# S181C.net
KiCad netlist of a schematic drawn in EAGLE
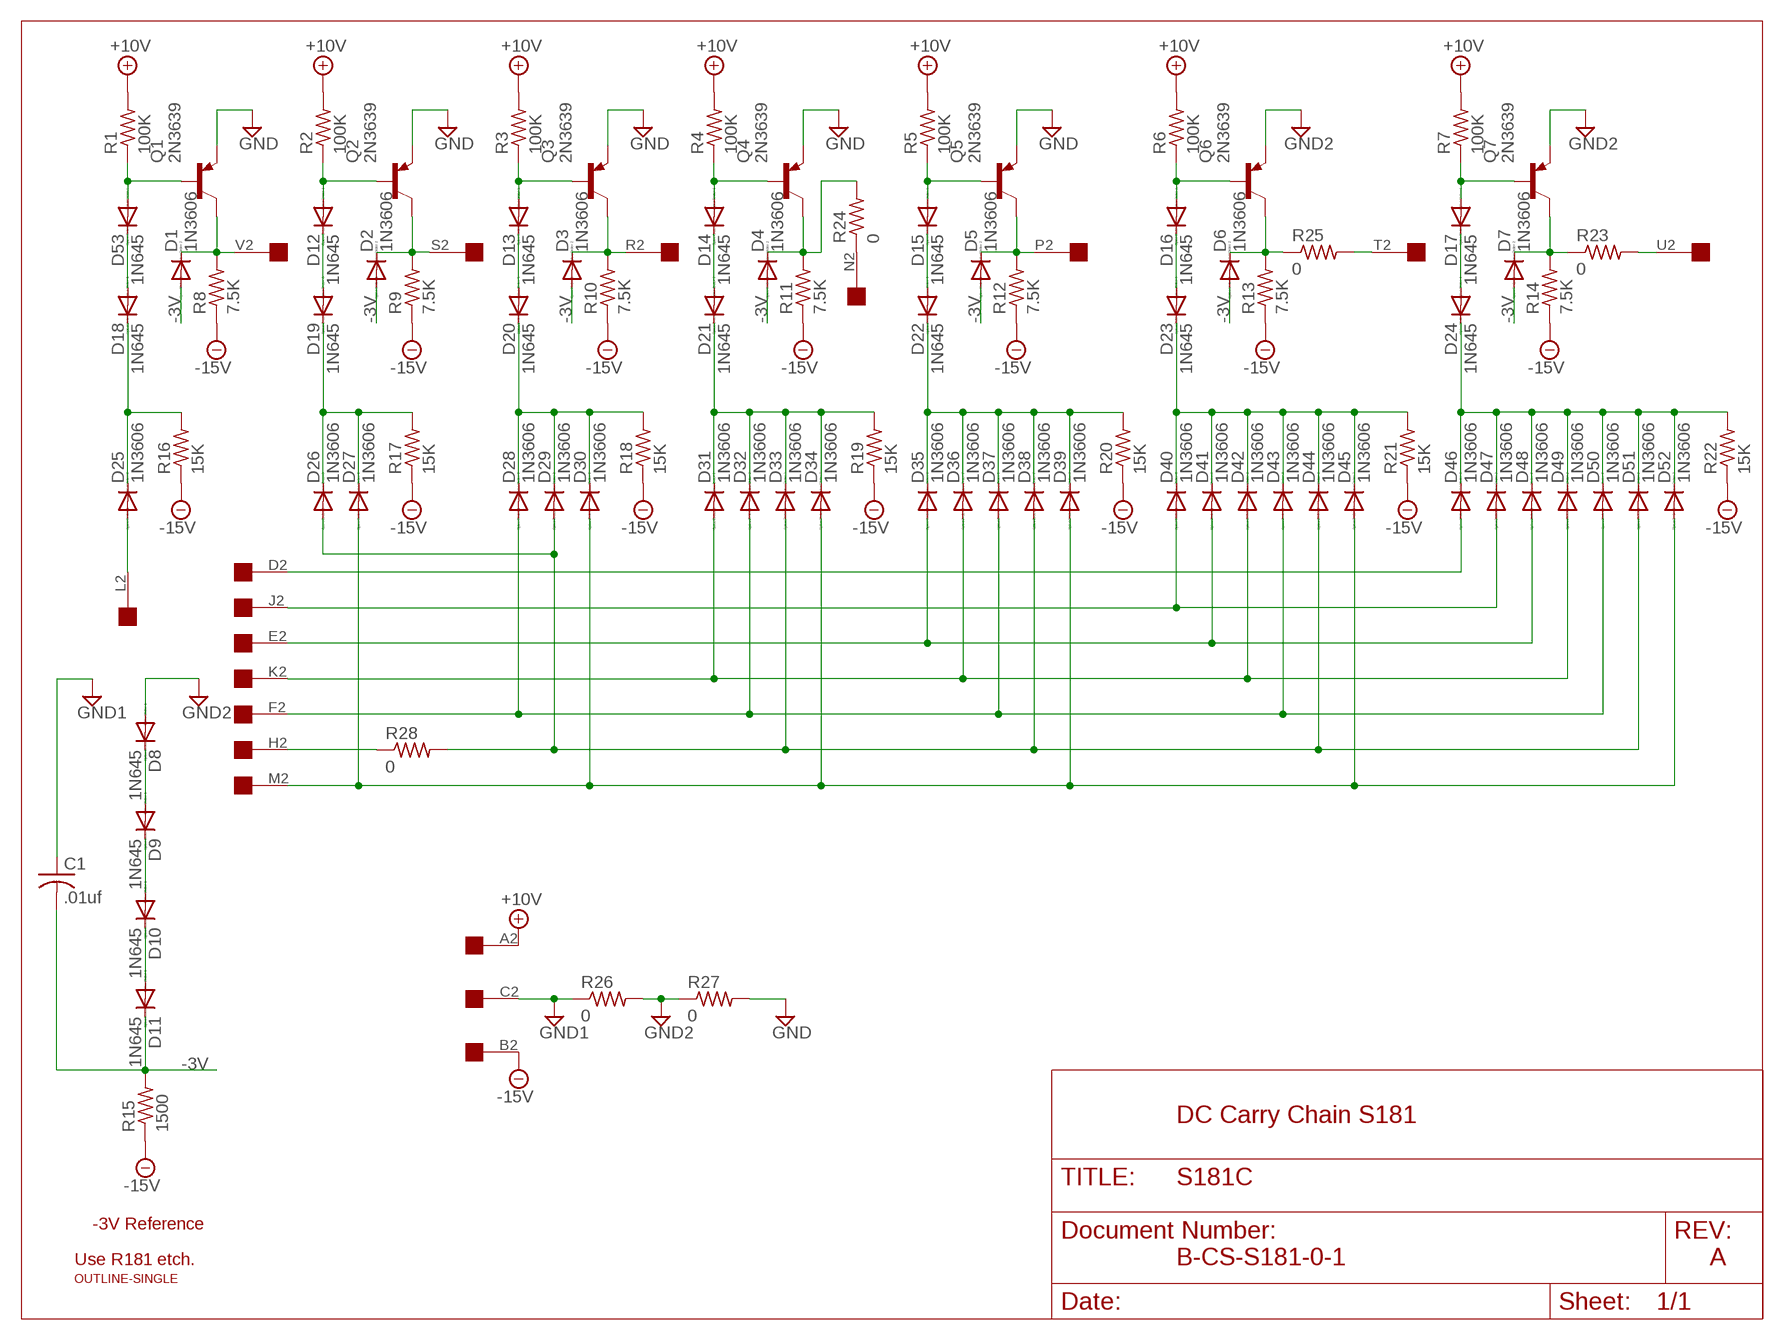
[diagram p0: schematic, sheet 1]

(export (version "E")
  (design (tool "Eeschema 10.0.6"))
  (components
    (comp (ref "C1")
      (value ".01uf")
      (footprint "eagle-import:C050-025X075")
      (libsource (lib "eagle-import") (part "C-US050-025X075"))
    )
    (comp (ref "D1")
      (value "1N3606")
      (footprint "eagle-import:DO35-10")
      (libsource (lib "eagle-import") (part "1N4148DO35-10"))
    )
    (comp (ref "D2")
      (value "1N3606")
      (footprint "eagle-import:DO35-10")
      (libsource (lib "eagle-import") (part "1N4148DO35-10"))
    )
    (comp (ref "D3")
      (value "1N3606")
      (footprint "eagle-import:DO35-10")
      (libsource (lib "eagle-import") (part "1N4148DO35-10"))
    )
    (comp (ref "D4")
      (value "1N3606")
      (footprint "eagle-import:DO35-10")
      (libsource (lib "eagle-import") (part "1N4148DO35-10"))
    )
    (comp (ref "D5")
      (value "1N3606")
      (footprint "eagle-import:DO35-10")
      (libsource (lib "eagle-import") (part "1N4148DO35-10"))
    )
    (comp (ref "D6")
      (value "1N3606")
      (footprint "eagle-import:DO35-10")
      (libsource (lib "eagle-import") (part "1N4148DO35-10"))
    )
    (comp (ref "D7")
      (value "1N3606")
      (footprint "eagle-import:DO35-10")
      (libsource (lib "eagle-import") (part "1N4148DO35-10"))
    )
    (comp (ref "D8")
      (value "1N645")
      (footprint "eagle-import:DO35-10")
      (libsource (lib "eagle-import") (part "1N4148DO35-10"))
    )
    (comp (ref "D9")
      (value "1N645")
      (footprint "eagle-import:DO35-10")
      (libsource (lib "eagle-import") (part "1N4148DO35-10"))
    )
    (comp (ref "D10")
      (value "1N645")
      (footprint "eagle-import:DO35-10")
      (libsource (lib "eagle-import") (part "1N4148DO35-10"))
    )
    (comp (ref "D11")
      (value "1N645")
      (footprint "eagle-import:DO35-10")
      (libsource (lib "eagle-import") (part "1N4148DO35-10"))
    )
    (comp (ref "D12")
      (value "1N645")
      (footprint "eagle-import:DO35-10")
      (libsource (lib "eagle-import") (part "1N4148DO35-10"))
    )
    (comp (ref "D13")
      (value "1N645")
      (footprint "eagle-import:DO35-10")
      (libsource (lib "eagle-import") (part "1N4148DO35-10"))
    )
    (comp (ref "D14")
      (value "1N645")
      (footprint "eagle-import:DO35-10")
      (libsource (lib "eagle-import") (part "1N4148DO35-10"))
    )
    (comp (ref "D15")
      (value "1N645")
      (footprint "eagle-import:DO35-10")
      (libsource (lib "eagle-import") (part "1N4148DO35-10"))
    )
    (comp (ref "D16")
      (value "1N645")
      (footprint "eagle-import:DO35-10")
      (libsource (lib "eagle-import") (part "1N4148DO35-10"))
    )
    (comp (ref "D17")
      (value "1N645")
      (footprint "eagle-import:DO35-10")
      (libsource (lib "eagle-import") (part "1N4148DO35-10"))
    )
    (comp (ref "D18")
      (value "1N645")
      (footprint "eagle-import:DO35-10")
      (libsource (lib "eagle-import") (part "1N4148DO35-10"))
    )
    (comp (ref "D19")
      (value "1N645")
      (footprint "eagle-import:DO35-10")
      (libsource (lib "eagle-import") (part "1N4148DO35-10"))
    )
    (comp (ref "D20")
      (value "1N645")
      (footprint "eagle-import:DO35-10")
      (libsource (lib "eagle-import") (part "1N4148DO35-10"))
    )
    (comp (ref "D21")
      (value "1N645")
      (footprint "eagle-import:DO35-10")
      (libsource (lib "eagle-import") (part "1N4148DO35-10"))
    )
    (comp (ref "D22")
      (value "1N645")
      (footprint "eagle-import:DO35-10")
      (libsource (lib "eagle-import") (part "1N4148DO35-10"))
    )
    (comp (ref "D23")
      (value "1N645")
      (footprint "eagle-import:DO35-10")
      (libsource (lib "eagle-import") (part "1N4148DO35-10"))
    )
    (comp (ref "D24")
      (value "1N645")
      (footprint "eagle-import:DO35-10")
      (libsource (lib "eagle-import") (part "1N4148DO35-10"))
    )
    (comp (ref "D25")
      (value "1N3606")
      (footprint "eagle-import:DO35-10")
      (libsource (lib "eagle-import") (part "1N4148DO35-10"))
    )
    (comp (ref "D26")
      (value "1N3606")
      (footprint "eagle-import:DO35-10")
      (libsource (lib "eagle-import") (part "1N4148DO35-10"))
    )
    (comp (ref "D27")
      (value "1N3606")
      (footprint "eagle-import:DO35-10")
      (libsource (lib "eagle-import") (part "1N4148DO35-10"))
    )
    (comp (ref "D28")
      (value "1N3606")
      (footprint "eagle-import:DO35-10")
      (libsource (lib "eagle-import") (part "1N4148DO35-10"))
    )
    (comp (ref "D29")
      (value "1N3606")
      (footprint "eagle-import:DO35-10")
      (libsource (lib "eagle-import") (part "1N4148DO35-10"))
    )
    (comp (ref "D30")
      (value "1N3606")
      (footprint "eagle-import:DO35-10")
      (libsource (lib "eagle-import") (part "1N4148DO35-10"))
    )
    (comp (ref "D31")
      (value "1N3606")
      (footprint "eagle-import:DO35-10")
      (libsource (lib "eagle-import") (part "1N4148DO35-10"))
    )
    (comp (ref "D32")
      (value "1N3606")
      (footprint "eagle-import:DO35-10")
      (libsource (lib "eagle-import") (part "1N4148DO35-10"))
    )
    (comp (ref "D33")
      (value "1N3606")
      (footprint "eagle-import:DO35-10")
      (libsource (lib "eagle-import") (part "1N4148DO35-10"))
    )
    (comp (ref "D34")
      (value "1N3606")
      (footprint "eagle-import:DO35-10")
      (libsource (lib "eagle-import") (part "1N4148DO35-10"))
    )
    (comp (ref "D35")
      (value "1N3606")
      (footprint "eagle-import:DO35-10")
      (libsource (lib "eagle-import") (part "1N4148DO35-10"))
    )
    (comp (ref "D36")
      (value "1N3606")
      (footprint "eagle-import:DO35-10")
      (libsource (lib "eagle-import") (part "1N4148DO35-10"))
    )
    (comp (ref "D37")
      (value "1N3606")
      (footprint "eagle-import:DO35-10")
      (libsource (lib "eagle-import") (part "1N4148DO35-10"))
    )
    (comp (ref "D38")
      (value "1N3606")
      (footprint "eagle-import:DO35-10")
      (libsource (lib "eagle-import") (part "1N4148DO35-10"))
    )
    (comp (ref "D39")
      (value "1N3606")
      (footprint "eagle-import:DO35-10")
      (libsource (lib "eagle-import") (part "1N4148DO35-10"))
    )
    (comp (ref "D40")
      (value "1N3606")
      (footprint "eagle-import:DO35-10")
      (libsource (lib "eagle-import") (part "1N4148DO35-10"))
    )
    (comp (ref "D41")
      (value "1N3606")
      (footprint "eagle-import:DO35-10")
      (libsource (lib "eagle-import") (part "1N4148DO35-10"))
    )
    (comp (ref "D42")
      (value "1N3606")
      (footprint "eagle-import:DO35-10")
      (libsource (lib "eagle-import") (part "1N4148DO35-10"))
    )
    (comp (ref "D43")
      (value "1N3606")
      (footprint "eagle-import:DO35-10")
      (libsource (lib "eagle-import") (part "1N4148DO35-10"))
    )
    (comp (ref "D44")
      (value "1N3606")
      (footprint "eagle-import:DO35-10")
      (libsource (lib "eagle-import") (part "1N4148DO35-10"))
    )
    (comp (ref "D45")
      (value "1N3606")
      (footprint "eagle-import:DO35-10")
      (libsource (lib "eagle-import") (part "1N4148DO35-10"))
    )
    (comp (ref "D46")
      (value "1N3606")
      (footprint "eagle-import:DO35-10")
      (libsource (lib "eagle-import") (part "1N4148DO35-10"))
    )
    (comp (ref "D47")
      (value "1N3606")
      (footprint "eagle-import:DO35-10")
      (libsource (lib "eagle-import") (part "1N4148DO35-10"))
    )
    (comp (ref "D48")
      (value "1N3606")
      (footprint "eagle-import:DO35-10")
      (libsource (lib "eagle-import") (part "1N4148DO35-10"))
    )
    (comp (ref "D49")
      (value "1N3606")
      (footprint "eagle-import:DO35-10")
      (libsource (lib "eagle-import") (part "1N4148DO35-10"))
    )
    (comp (ref "D50")
      (value "1N3606")
      (footprint "eagle-import:DO35-10")
      (libsource (lib "eagle-import") (part "1N4148DO35-10"))
    )
    (comp (ref "D51")
      (value "1N3606")
      (footprint "eagle-import:DO35-10")
      (libsource (lib "eagle-import") (part "1N4148DO35-10"))
    )
    (comp (ref "D52")
      (value "1N3606")
      (footprint "eagle-import:DO35-10")
      (libsource (lib "eagle-import") (part "1N4148DO35-10"))
    )
    (comp (ref "D53")
      (value "1N645")
      (footprint "eagle-import:DO35-10")
      (libsource (lib "eagle-import") (part "1N4148DO35-10"))
    )
    (comp (ref "Q1")
      (value "2N3639")
      (footprint "eagle-import:TO39")
      (libsource (lib "eagle-import") (part "2N3637"))
    )
    (comp (ref "Q2")
      (value "2N3639")
      (footprint "eagle-import:TO39")
      (libsource (lib "eagle-import") (part "2N3637"))
    )
    (comp (ref "Q3")
      (value "2N3639")
      (footprint "eagle-import:TO39")
      (libsource (lib "eagle-import") (part "2N3637"))
    )
    (comp (ref "Q4")
      (value "2N3639")
      (footprint "eagle-import:TO39")
      (libsource (lib "eagle-import") (part "2N3637"))
    )
    (comp (ref "Q5")
      (value "2N3639")
      (footprint "eagle-import:TO39")
      (libsource (lib "eagle-import") (part "2N3637"))
    )
    (comp (ref "Q6")
      (value "2N3639")
      (footprint "eagle-import:TO39")
      (libsource (lib "eagle-import") (part "2N3637"))
    )
    (comp (ref "Q7")
      (value "2N3639")
      (footprint "eagle-import:TO39")
      (libsource (lib "eagle-import") (part "2N3637"))
    )
    (comp (ref "R1")
      (value "100K")
      (footprint "eagle-import:0207_10")
      (libsource (lib "eagle-import") (part "R-US_0207/10"))
    )
    (comp (ref "R2")
      (value "100K")
      (footprint "eagle-import:0207_10")
      (libsource (lib "eagle-import") (part "R-US_0207/10"))
    )
    (comp (ref "R3")
      (value "100K")
      (footprint "eagle-import:0207_10")
      (libsource (lib "eagle-import") (part "R-US_0207/10"))
    )
    (comp (ref "R4")
      (value "100K")
      (footprint "eagle-import:0207_10")
      (libsource (lib "eagle-import") (part "R-US_0207/10"))
    )
    (comp (ref "R5")
      (value "100K")
      (footprint "eagle-import:0207_10")
      (libsource (lib "eagle-import") (part "R-US_0207/10"))
    )
    (comp (ref "R6")
      (value "100K")
      (footprint "eagle-import:0207_10")
      (libsource (lib "eagle-import") (part "R-US_0207/10"))
    )
    (comp (ref "R7")
      (value "100K")
      (footprint "eagle-import:0207_10")
      (libsource (lib "eagle-import") (part "R-US_0207/10"))
    )
    (comp (ref "R8")
      (value "7.5K")
      (footprint "eagle-import:0207_10")
      (libsource (lib "eagle-import") (part "R-US_0207/10"))
    )
    (comp (ref "R9")
      (value "7.5K")
      (footprint "eagle-import:0207_10")
      (libsource (lib "eagle-import") (part "R-US_0207/10"))
    )
    (comp (ref "R10")
      (value "7.5K")
      (footprint "eagle-import:0207_10")
      (libsource (lib "eagle-import") (part "R-US_0207/10"))
    )
    (comp (ref "R11")
      (value "7.5K")
      (footprint "eagle-import:0207_10")
      (libsource (lib "eagle-import") (part "R-US_0207/10"))
    )
    (comp (ref "R12")
      (value "7.5K")
      (footprint "eagle-import:0207_10")
      (libsource (lib "eagle-import") (part "R-US_0207/10"))
    )
    (comp (ref "R13")
      (value "7.5K")
      (footprint "eagle-import:0207_10")
      (libsource (lib "eagle-import") (part "R-US_0207/10"))
    )
    (comp (ref "R14")
      (value "7.5K")
      (footprint "eagle-import:0207_10")
      (libsource (lib "eagle-import") (part "R-US_0207/10"))
    )
    (comp (ref "R15")
      (value "1500")
      (footprint "eagle-import:0207_10")
      (libsource (lib "eagle-import") (part "R-US_0207/10"))
    )
    (comp (ref "R16")
      (value "15K")
      (footprint "eagle-import:0207_10")
      (libsource (lib "eagle-import") (part "R-US_0207/10"))
    )
    (comp (ref "R17")
      (value "15K")
      (footprint "eagle-import:0207_10")
      (libsource (lib "eagle-import") (part "R-US_0207/10"))
    )
    (comp (ref "R18")
      (value "15K")
      (footprint "eagle-import:0207_10")
      (libsource (lib "eagle-import") (part "R-US_0207/10"))
    )
    (comp (ref "R19")
      (value "15K")
      (footprint "eagle-import:0207_10")
      (libsource (lib "eagle-import") (part "R-US_0207/10"))
    )
    (comp (ref "R20")
      (value "15K")
      (footprint "eagle-import:0207_10")
      (libsource (lib "eagle-import") (part "R-US_0207/10"))
    )
    (comp (ref "R21")
      (value "15K")
      (footprint "eagle-import:0207_10")
      (libsource (lib "eagle-import") (part "R-US_0207/10"))
    )
    (comp (ref "R22")
      (value "15K")
      (footprint "eagle-import:0207_10")
      (libsource (lib "eagle-import") (part "R-US_0207/10"))
    )
    (comp (ref "R23")
      (value "0")
      (footprint "eagle-import:0207_10")
      (libsource (lib "eagle-import") (part "R-US_0207/10"))
    )
    (comp (ref "R24")
      (value "0")
      (footprint "eagle-import:0207_10")
      (libsource (lib "eagle-import") (part "R-US_0207/10"))
    )
    (comp (ref "R25")
      (value "0")
      (footprint "eagle-import:0207_10")
      (libsource (lib "eagle-import") (part "R-US_0207/10"))
    )
    (comp (ref "R26")
      (value "0")
      (footprint "eagle-import:0207_10")
      (libsource (lib "eagle-import") (part "R-US_0207/10"))
    )
    (comp (ref "R27")
      (value "0")
      (footprint "eagle-import:0207_10")
      (libsource (lib "eagle-import") (part "R-US_0207/10"))
    )
    (comp (ref "R28")
      (value "0")
      (footprint "eagle-import:0207_10")
      (libsource (lib "eagle-import") (part "R-US_0207/10"))
    )
    (comp (ref "U$1")
      (value "OUTLINE-SINGLE")
      (footprint "eagle-import:SINGLE")
      (libsource (lib "eagle-import") (part "OUTLINE-SINGLE"))
    )
    (comp (ref "U$2")
      (value "EDGE-1")
      (footprint "eagle-import:EDGE-CON1")
      (libsource (lib "eagle-import") (part "EDGE-1"))
    )
  )
  (nets
    (net (code "1") (name "+10V") (class "Default")
      (node (ref "R1") (pin "2") (pinfunction "2_2") (pintype "passive"))
      (node (ref "R2") (pin "2") (pinfunction "2_2") (pintype "passive"))
      (node (ref "R3") (pin "2") (pinfunction "2_2") (pintype "passive"))
      (node (ref "R4") (pin "2") (pinfunction "2_2") (pintype "passive"))
      (node (ref "R5") (pin "2") (pinfunction "2_2") (pintype "passive"))
      (node (ref "R6") (pin "2") (pinfunction "2_2") (pintype "passive"))
      (node (ref "R7") (pin "2") (pinfunction "2_2") (pintype "passive"))
      (node (ref "U$2") (pin "A2") (pinfunction "1_A2") (pintype "bidirectional"))
    )
    (net (code "2") (name "-15V") (class "Default")
      (node (ref "R10") (pin "1") (pinfunction "1_1") (pintype "passive"))
      (node (ref "R11") (pin "1") (pinfunction "1_1") (pintype "passive"))
      (node (ref "R12") (pin "1") (pinfunction "1_1") (pintype "passive"))
      (node (ref "R13") (pin "1") (pinfunction "1_1") (pintype "passive"))
      (node (ref "R14") (pin "1") (pinfunction "1_1") (pintype "passive"))
      (node (ref "R15") (pin "1") (pinfunction "1_1") (pintype "passive"))
      (node (ref "R16") (pin "1") (pinfunction "1_1") (pintype "passive"))
      (node (ref "R17") (pin "1") (pinfunction "1_1") (pintype "passive"))
      (node (ref "R18") (pin "1") (pinfunction "1_1") (pintype "passive"))
      (node (ref "R19") (pin "1") (pinfunction "1_1") (pintype "passive"))
      (node (ref "R20") (pin "1") (pinfunction "1_1") (pintype "passive"))
      (node (ref "R21") (pin "1") (pinfunction "1_1") (pintype "passive"))
      (node (ref "R22") (pin "1") (pinfunction "1_1") (pintype "passive"))
      (node (ref "R8") (pin "1") (pinfunction "1_1") (pintype "passive"))
      (node (ref "R9") (pin "1") (pinfunction "1_1") (pintype "passive"))
      (node (ref "U$2") (pin "B2") (pinfunction "1_B2") (pintype "bidirectional"))
    )
    (net (code "3") (name "/-3V") (class "Default")
      (node (ref "C1") (pin "2") (pinfunction "2_2") (pintype "passive"))
      (node (ref "D1") (pin "A") (pinfunction "A_A") (pintype "passive"))
      (node (ref "D11") (pin "C") (pinfunction "C_C") (pintype "passive"))
      (node (ref "D2") (pin "A") (pinfunction "A_A") (pintype "passive"))
      (node (ref "D3") (pin "A") (pinfunction "A_A") (pintype "passive"))
      (node (ref "D4") (pin "A") (pinfunction "A_A") (pintype "passive"))
      (node (ref "D5") (pin "A") (pinfunction "A_A") (pintype "passive"))
      (node (ref "D6") (pin "A") (pinfunction "A_A") (pintype "passive"))
      (node (ref "D7") (pin "A") (pinfunction "A_A") (pintype "passive"))
      (node (ref "R15") (pin "2") (pinfunction "2_2") (pintype "passive"))
    )
    (net (code "4") (name "GND") (class "Default")
      (node (ref "Q1") (pin "1") (pinfunction "E_1") (pintype "passive"))
      (node (ref "Q2") (pin "1") (pinfunction "E_1") (pintype "passive"))
      (node (ref "Q3") (pin "1") (pinfunction "E_1") (pintype "passive"))
      (node (ref "Q4") (pin "1") (pinfunction "E_1") (pintype "passive"))
      (node (ref "Q5") (pin "1") (pinfunction "E_1") (pintype "passive"))
      (node (ref "R27") (pin "2") (pinfunction "2_2") (pintype "passive"))
    )
    (net (code "5") (name "GND1") (class "Default")
      (node (ref "C1") (pin "1") (pinfunction "1_1") (pintype "passive"))
      (node (ref "R26") (pin "1") (pinfunction "1_1") (pintype "passive"))
      (node (ref "U$2") (pin "C2") (pinfunction "1_C2") (pintype "bidirectional"))
    )
    (net (code "6") (name "GND2") (class "Default")
      (node (ref "D8") (pin "A") (pinfunction "A_A") (pintype "passive"))
      (node (ref "Q6") (pin "1") (pinfunction "E_1") (pintype "passive"))
      (node (ref "Q7") (pin "1") (pinfunction "E_1") (pintype "passive"))
      (node (ref "R26") (pin "2") (pinfunction "2_2") (pintype "passive"))
      (node (ref "R27") (pin "1") (pinfunction "1_1") (pintype "passive"))
    )
    (net (code "7") (name "Net-(D8-PadC)") (class "Default")
      (node (ref "D8") (pin "C") (pinfunction "C_C") (pintype "passive"))
      (node (ref "D9") (pin "A") (pinfunction "A_A") (pintype "passive"))
    )
    (net (code "8") (name "Net-(D10-PadA)") (class "Default")
      (node (ref "D10") (pin "A") (pinfunction "A_A") (pintype "passive"))
      (node (ref "D9") (pin "C") (pinfunction "C_C") (pintype "passive"))
    )
    (net (code "9") (name "Net-(D10-PadC)") (class "Default")
      (node (ref "D10") (pin "C") (pinfunction "C_C") (pintype "passive"))
      (node (ref "D11") (pin "A") (pinfunction "A_A") (pintype "passive"))
    )
    (net (code "10") (name "Net-(D12-PadC)") (class "Default")
      (node (ref "D12") (pin "C") (pinfunction "C_C") (pintype "passive"))
      (node (ref "D19") (pin "A") (pinfunction "A_A") (pintype "passive"))
    )
    (net (code "11") (name "Net-(D13-PadC)") (class "Default")
      (node (ref "D13") (pin "C") (pinfunction "C_C") (pintype "passive"))
      (node (ref "D20") (pin "A") (pinfunction "A_A") (pintype "passive"))
    )
    (net (code "12") (name "Net-(D14-PadC)") (class "Default")
      (node (ref "D14") (pin "C") (pinfunction "C_C") (pintype "passive"))
      (node (ref "D21") (pin "A") (pinfunction "A_A") (pintype "passive"))
    )
    (net (code "13") (name "Net-(D15-PadC)") (class "Default")
      (node (ref "D15") (pin "C") (pinfunction "C_C") (pintype "passive"))
      (node (ref "D22") (pin "A") (pinfunction "A_A") (pintype "passive"))
    )
    (net (code "14") (name "Net-(D16-PadC)") (class "Default")
      (node (ref "D16") (pin "C") (pinfunction "C_C") (pintype "passive"))
      (node (ref "D23") (pin "A") (pinfunction "A_A") (pintype "passive"))
    )
    (net (code "15") (name "Net-(D17-PadC)") (class "Default")
      (node (ref "D17") (pin "C") (pinfunction "C_C") (pintype "passive"))
      (node (ref "D24") (pin "A") (pinfunction "A_A") (pintype "passive"))
    )
    (net (code "16") (name "Net-(D18-PadA)") (class "Default")
      (node (ref "D18") (pin "A") (pinfunction "A_A") (pintype "passive"))
      (node (ref "D53") (pin "C") (pinfunction "C_C") (pintype "passive"))
    )
    (net (code "17") (name "Net-(D18-PadC)") (class "Default")
      (node (ref "D18") (pin "C") (pinfunction "C_C") (pintype "passive"))
      (node (ref "D25") (pin "C") (pinfunction "C_C") (pintype "passive"))
      (node (ref "R16") (pin "2") (pinfunction "2_2") (pintype "passive"))
    )
    (net (code "18") (name "Net-(D19-PadC)") (class "Default")
      (node (ref "D19") (pin "C") (pinfunction "C_C") (pintype "passive"))
      (node (ref "D26") (pin "C") (pinfunction "C_C") (pintype "passive"))
      (node (ref "D27") (pin "C") (pinfunction "C_C") (pintype "passive"))
      (node (ref "R17") (pin "2") (pinfunction "2_2") (pintype "passive"))
    )
    (net (code "19") (name "Net-(D20-PadC)") (class "Default")
      (node (ref "D20") (pin "C") (pinfunction "C_C") (pintype "passive"))
      (node (ref "D28") (pin "C") (pinfunction "C_C") (pintype "passive"))
      (node (ref "D29") (pin "C") (pinfunction "C_C") (pintype "passive"))
      (node (ref "D30") (pin "C") (pinfunction "C_C") (pintype "passive"))
      (node (ref "R18") (pin "2") (pinfunction "2_2") (pintype "passive"))
    )
    (net (code "20") (name "Net-(D21-PadC)") (class "Default")
      (node (ref "D21") (pin "C") (pinfunction "C_C") (pintype "passive"))
      (node (ref "D31") (pin "C") (pinfunction "C_C") (pintype "passive"))
      (node (ref "D32") (pin "C") (pinfunction "C_C") (pintype "passive"))
      (node (ref "D33") (pin "C") (pinfunction "C_C") (pintype "passive"))
      (node (ref "D34") (pin "C") (pinfunction "C_C") (pintype "passive"))
      (node (ref "R19") (pin "2") (pinfunction "2_2") (pintype "passive"))
    )
    (net (code "21") (name "Net-(D22-PadC)") (class "Default")
      (node (ref "D22") (pin "C") (pinfunction "C_C") (pintype "passive"))
      (node (ref "D35") (pin "C") (pinfunction "C_C") (pintype "passive"))
      (node (ref "D36") (pin "C") (pinfunction "C_C") (pintype "passive"))
      (node (ref "D37") (pin "C") (pinfunction "C_C") (pintype "passive"))
      (node (ref "D38") (pin "C") (pinfunction "C_C") (pintype "passive"))
      (node (ref "D39") (pin "C") (pinfunction "C_C") (pintype "passive"))
      (node (ref "R20") (pin "2") (pinfunction "2_2") (pintype "passive"))
    )
    (net (code "22") (name "Net-(D23-PadC)") (class "Default")
      (node (ref "D23") (pin "C") (pinfunction "C_C") (pintype "passive"))
      (node (ref "D40") (pin "C") (pinfunction "C_C") (pintype "passive"))
      (node (ref "D41") (pin "C") (pinfunction "C_C") (pintype "passive"))
      (node (ref "D42") (pin "C") (pinfunction "C_C") (pintype "passive"))
      (node (ref "D43") (pin "C") (pinfunction "C_C") (pintype "passive"))
      (node (ref "D44") (pin "C") (pinfunction "C_C") (pintype "passive"))
      (node (ref "D45") (pin "C") (pinfunction "C_C") (pintype "passive"))
      (node (ref "R21") (pin "2") (pinfunction "2_2") (pintype "passive"))
    )
    (net (code "23") (name "Net-(D24-PadC)") (class "Default")
      (node (ref "D24") (pin "C") (pinfunction "C_C") (pintype "passive"))
      (node (ref "D46") (pin "C") (pinfunction "C_C") (pintype "passive"))
      (node (ref "D47") (pin "C") (pinfunction "C_C") (pintype "passive"))
      (node (ref "D48") (pin "C") (pinfunction "C_C") (pintype "passive"))
      (node (ref "D49") (pin "C") (pinfunction "C_C") (pintype "passive"))
      (node (ref "D50") (pin "C") (pinfunction "C_C") (pintype "passive"))
      (node (ref "D51") (pin "C") (pinfunction "C_C") (pintype "passive"))
      (node (ref "D52") (pin "C") (pinfunction "C_C") (pintype "passive"))
      (node (ref "R22") (pin "2") (pinfunction "2_2") (pintype "passive"))
    )
    (net (code "24") (name "Net-(D26-PadA)") (class "Default")
      (node (ref "D26") (pin "A") (pinfunction "A_A") (pintype "passive"))
      (node (ref "D29") (pin "A") (pinfunction "A_A") (pintype "passive"))
      (node (ref "D33") (pin "A") (pinfunction "A_A") (pintype "passive"))
      (node (ref "D38") (pin "A") (pinfunction "A_A") (pintype "passive"))
      (node (ref "D44") (pin "A") (pinfunction "A_A") (pintype "passive"))
      (node (ref "D51") (pin "A") (pinfunction "A_A") (pintype "passive"))
      (node (ref "R28") (pin "2") (pinfunction "2_2") (pintype "passive"))
    )
    (net (code "25") (name "Net-(Q1-B)") (class "Default")
      (node (ref "D53") (pin "A") (pinfunction "A_A") (pintype "passive"))
      (node (ref "Q1") (pin "2") (pinfunction "B_2") (pintype "passive"))
      (node (ref "R1") (pin "1") (pinfunction "1_1") (pintype "passive"))
    )
    (net (code "26") (name "Net-(Q1-C)") (class "Default")
      (node (ref "D1") (pin "C") (pinfunction "C_C") (pintype "passive"))
      (node (ref "Q1") (pin "3") (pinfunction "C_3") (pintype "passive"))
      (node (ref "R8") (pin "2") (pinfunction "2_2") (pintype "passive"))
      (node (ref "U$2") (pin "V2") (pinfunction "1_V2") (pintype "bidirectional"))
    )
    (net (code "27") (name "Net-(Q2-B)") (class "Default")
      (node (ref "D12") (pin "A") (pinfunction "A_A") (pintype "passive"))
      (node (ref "Q2") (pin "2") (pinfunction "B_2") (pintype "passive"))
      (node (ref "R2") (pin "1") (pinfunction "1_1") (pintype "passive"))
    )
    (net (code "28") (name "Net-(Q2-C)") (class "Default")
      (node (ref "D2") (pin "C") (pinfunction "C_C") (pintype "passive"))
      (node (ref "Q2") (pin "3") (pinfunction "C_3") (pintype "passive"))
      (node (ref "R9") (pin "2") (pinfunction "2_2") (pintype "passive"))
      (node (ref "U$2") (pin "S2") (pinfunction "1_S2") (pintype "bidirectional"))
    )
    (net (code "29") (name "Net-(Q3-B)") (class "Default")
      (node (ref "D13") (pin "A") (pinfunction "A_A") (pintype "passive"))
      (node (ref "Q3") (pin "2") (pinfunction "B_2") (pintype "passive"))
      (node (ref "R3") (pin "1") (pinfunction "1_1") (pintype "passive"))
    )
    (net (code "30") (name "Net-(Q3-C)") (class "Default")
      (node (ref "D3") (pin "C") (pinfunction "C_C") (pintype "passive"))
      (node (ref "Q3") (pin "3") (pinfunction "C_3") (pintype "passive"))
      (node (ref "R10") (pin "2") (pinfunction "2_2") (pintype "passive"))
      (node (ref "U$2") (pin "R2") (pinfunction "1_R2") (pintype "bidirectional"))
    )
    (net (code "31") (name "Net-(Q4-B)") (class "Default")
      (node (ref "D14") (pin "A") (pinfunction "A_A") (pintype "passive"))
      (node (ref "Q4") (pin "2") (pinfunction "B_2") (pintype "passive"))
      (node (ref "R4") (pin "1") (pinfunction "1_1") (pintype "passive"))
    )
    (net (code "32") (name "Net-(Q4-C)") (class "Default")
      (node (ref "D4") (pin "C") (pinfunction "C_C") (pintype "passive"))
      (node (ref "Q4") (pin "3") (pinfunction "C_3") (pintype "passive"))
      (node (ref "R11") (pin "2") (pinfunction "2_2") (pintype "passive"))
      (node (ref "R24") (pin "2") (pinfunction "2_2") (pintype "passive"))
    )
    (net (code "33") (name "Net-(Q5-B)") (class "Default")
      (node (ref "D15") (pin "A") (pinfunction "A_A") (pintype "passive"))
      (node (ref "Q5") (pin "2") (pinfunction "B_2") (pintype "passive"))
      (node (ref "R5") (pin "1") (pinfunction "1_1") (pintype "passive"))
    )
    (net (code "34") (name "Net-(Q5-C)") (class "Default")
      (node (ref "D5") (pin "C") (pinfunction "C_C") (pintype "passive"))
      (node (ref "Q5") (pin "3") (pinfunction "C_3") (pintype "passive"))
      (node (ref "R12") (pin "2") (pinfunction "2_2") (pintype "passive"))
      (node (ref "U$2") (pin "P2") (pinfunction "1_P2") (pintype "bidirectional"))
    )
    (net (code "35") (name "Net-(Q6-B)") (class "Default")
      (node (ref "D16") (pin "A") (pinfunction "A_A") (pintype "passive"))
      (node (ref "Q6") (pin "2") (pinfunction "B_2") (pintype "passive"))
      (node (ref "R6") (pin "1") (pinfunction "1_1") (pintype "passive"))
    )
    (net (code "36") (name "Net-(Q6-C)") (class "Default")
      (node (ref "D6") (pin "C") (pinfunction "C_C") (pintype "passive"))
      (node (ref "Q6") (pin "3") (pinfunction "C_3") (pintype "passive"))
      (node (ref "R13") (pin "2") (pinfunction "2_2") (pintype "passive"))
      (node (ref "R25") (pin "1") (pinfunction "1_1") (pintype "passive"))
    )
    (net (code "37") (name "Net-(Q7-B)") (class "Default")
      (node (ref "D17") (pin "A") (pinfunction "A_A") (pintype "passive"))
      (node (ref "Q7") (pin "2") (pinfunction "B_2") (pintype "passive"))
      (node (ref "R7") (pin "1") (pinfunction "1_1") (pintype "passive"))
    )
    (net (code "38") (name "Net-(Q7-C)") (class "Default")
      (node (ref "D7") (pin "C") (pinfunction "C_C") (pintype "passive"))
      (node (ref "Q7") (pin "3") (pinfunction "C_3") (pintype "passive"))
      (node (ref "R14") (pin "2") (pinfunction "2_2") (pintype "passive"))
      (node (ref "R23") (pin "1") (pinfunction "1_1") (pintype "passive"))
    )
    (net (code "39") (name "Net-(U$2D-1)") (class "Default")
      (node (ref "D46") (pin "A") (pinfunction "A_A") (pintype "passive"))
      (node (ref "U$2") (pin "D2") (pinfunction "1_D2") (pintype "bidirectional"))
    )
    (net (code "40") (name "Net-(U$2E-1)") (class "Default")
      (node (ref "D35") (pin "A") (pinfunction "A_A") (pintype "passive"))
      (node (ref "D41") (pin "A") (pinfunction "A_A") (pintype "passive"))
      (node (ref "D48") (pin "A") (pinfunction "A_A") (pintype "passive"))
      (node (ref "U$2") (pin "E2") (pinfunction "1_E2") (pintype "bidirectional"))
    )
    (net (code "41") (name "Net-(U$2F-1)") (class "Default")
      (node (ref "D28") (pin "A") (pinfunction "A_A") (pintype "passive"))
      (node (ref "D32") (pin "A") (pinfunction "A_A") (pintype "passive"))
      (node (ref "D37") (pin "A") (pinfunction "A_A") (pintype "passive"))
      (node (ref "D43") (pin "A") (pinfunction "A_A") (pintype "passive"))
      (node (ref "D50") (pin "A") (pinfunction "A_A") (pintype "passive"))
      (node (ref "U$2") (pin "F2") (pinfunction "1_F2") (pintype "bidirectional"))
    )
    (net (code "42") (name "Net-(U$2G-1)") (class "Default")
      (node (ref "R28") (pin "1") (pinfunction "1_1") (pintype "passive"))
      (node (ref "U$2") (pin "H2") (pinfunction "1_H2") (pintype "bidirectional"))
    )
    (net (code "43") (name "Net-(U$2H-1)") (class "Default")
      (node (ref "D40") (pin "A") (pinfunction "A_A") (pintype "passive"))
      (node (ref "D47") (pin "A") (pinfunction "A_A") (pintype "passive"))
      (node (ref "U$2") (pin "J2") (pinfunction "1_J2") (pintype "bidirectional"))
    )
    (net (code "44") (name "Net-(U$2I-1)") (class "Default")
      (node (ref "D31") (pin "A") (pinfunction "A_A") (pintype "passive"))
      (node (ref "D36") (pin "A") (pinfunction "A_A") (pintype "passive"))
      (node (ref "D42") (pin "A") (pinfunction "A_A") (pintype "passive"))
      (node (ref "D49") (pin "A") (pinfunction "A_A") (pintype "passive"))
      (node (ref "U$2") (pin "K2") (pinfunction "1_K2") (pintype "bidirectional"))
    )
    (net (code "45") (name "Net-(U$2J-1)") (class "Default")
      (node (ref "D25") (pin "A") (pinfunction "A_A") (pintype "passive"))
      (node (ref "U$2") (pin "L2") (pinfunction "1_L2") (pintype "bidirectional"))
    )
    (net (code "46") (name "Net-(U$2K-1)") (class "Default")
      (node (ref "D27") (pin "A") (pinfunction "A_A") (pintype "passive"))
      (node (ref "D30") (pin "A") (pinfunction "A_A") (pintype "passive"))
      (node (ref "D34") (pin "A") (pinfunction "A_A") (pintype "passive"))
      (node (ref "D39") (pin "A") (pinfunction "A_A") (pintype "passive"))
      (node (ref "D45") (pin "A") (pinfunction "A_A") (pintype "passive"))
      (node (ref "D52") (pin "A") (pinfunction "A_A") (pintype "passive"))
      (node (ref "U$2") (pin "M2") (pinfunction "1_M2") (pintype "bidirectional"))
    )
    (net (code "47") (name "Net-(U$2L-1)") (class "Default")
      (node (ref "R24") (pin "1") (pinfunction "1_1") (pintype "passive"))
      (node (ref "U$2") (pin "N2") (pinfunction "1_N2") (pintype "bidirectional"))
    )
    (net (code "48") (name "Net-(U$2P-1)") (class "Default")
      (node (ref "R25") (pin "2") (pinfunction "2_2") (pintype "passive"))
      (node (ref "U$2") (pin "T2") (pinfunction "1_T2") (pintype "bidirectional"))
    )
    (net (code "49") (name "Net-(U$2Q-1)") (class "Default")
      (node (ref "R23") (pin "2") (pinfunction "2_2") (pintype "passive"))
      (node (ref "U$2") (pin "U2") (pinfunction "1_U2") (pintype "bidirectional"))
    )
  )
)
